# RF-PCB.net
KiCad netlist of a schematic drawn in EAGLE
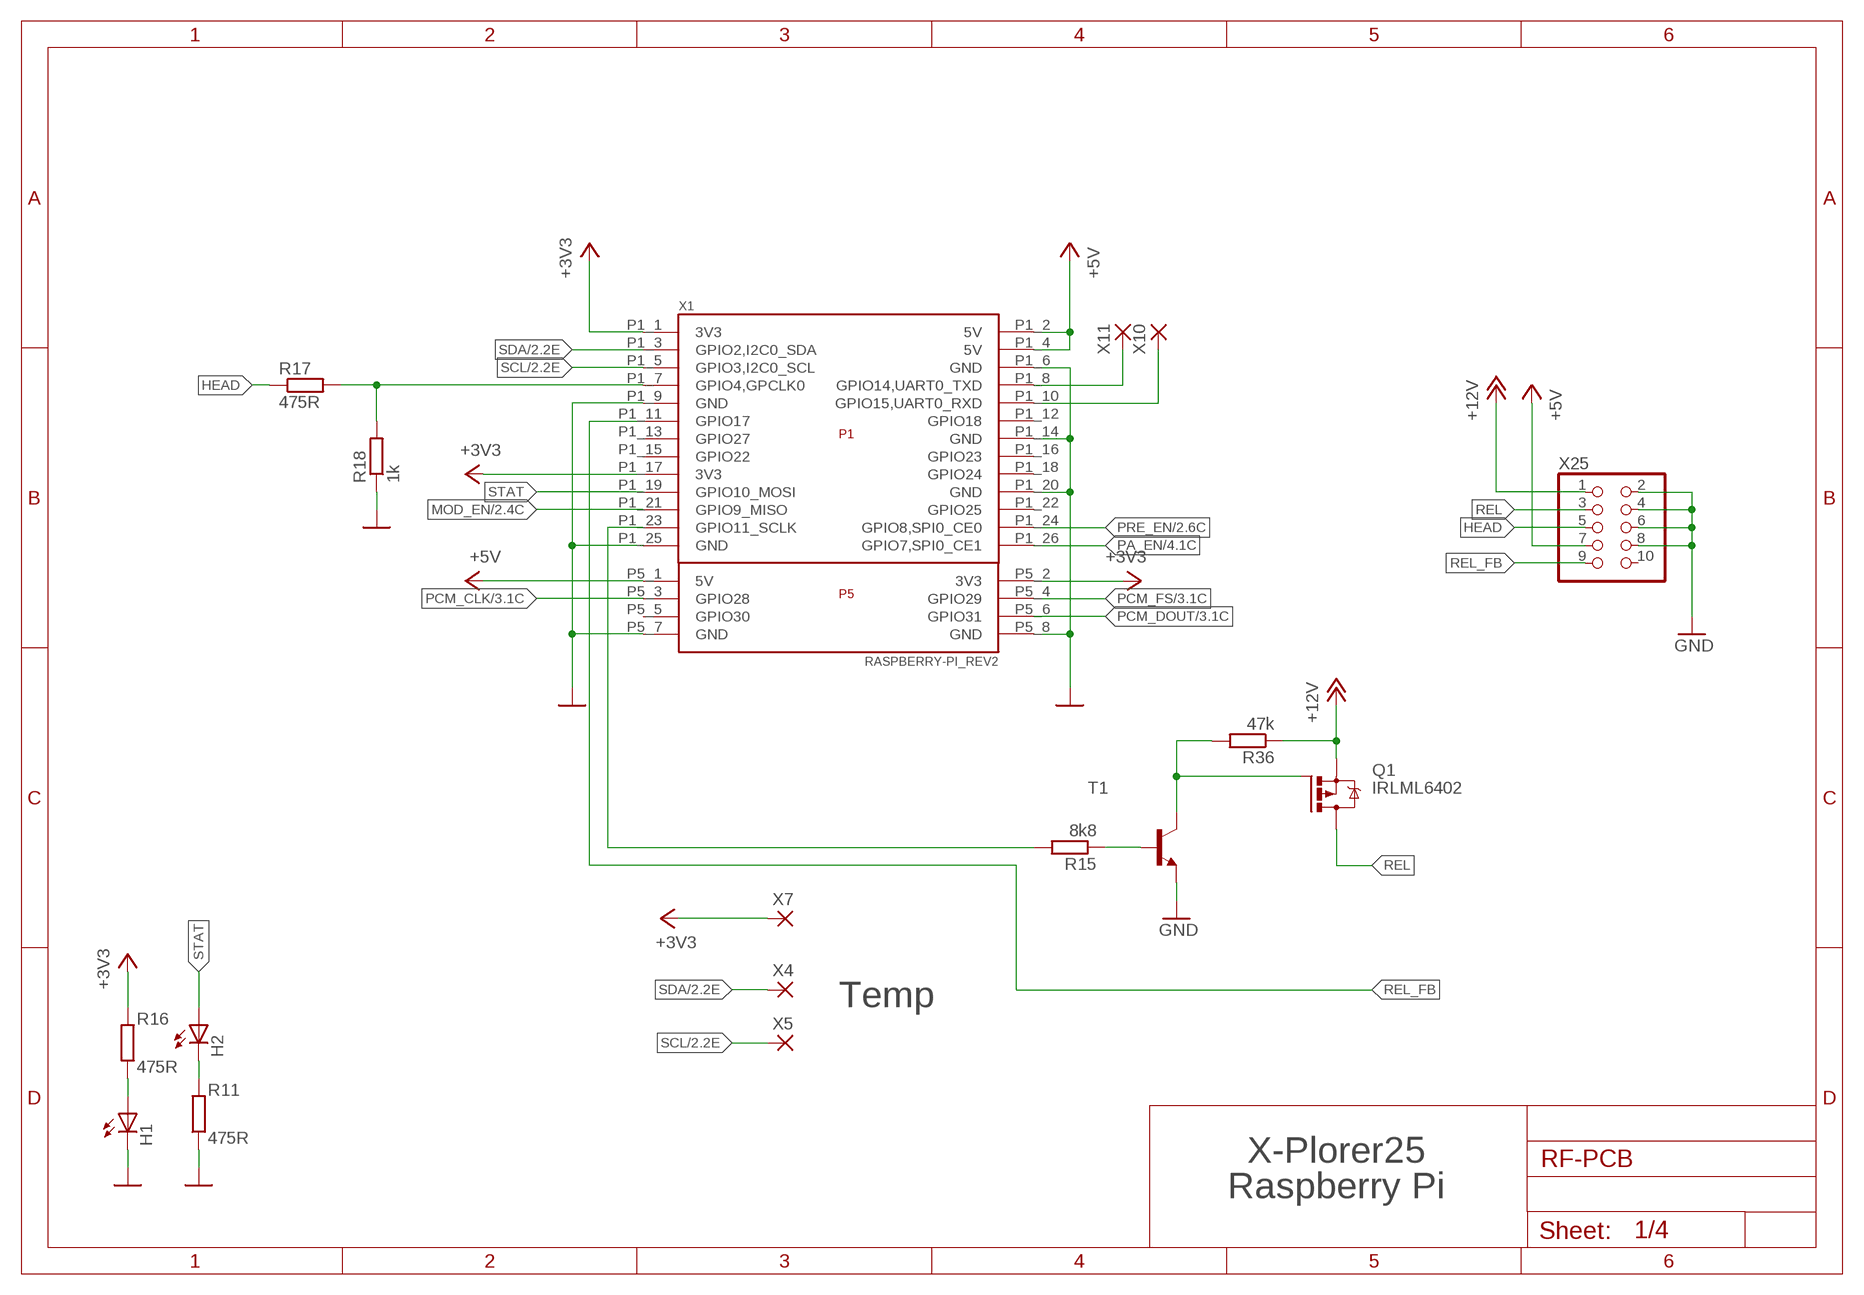
[diagram p0: schematic, sheet 1]
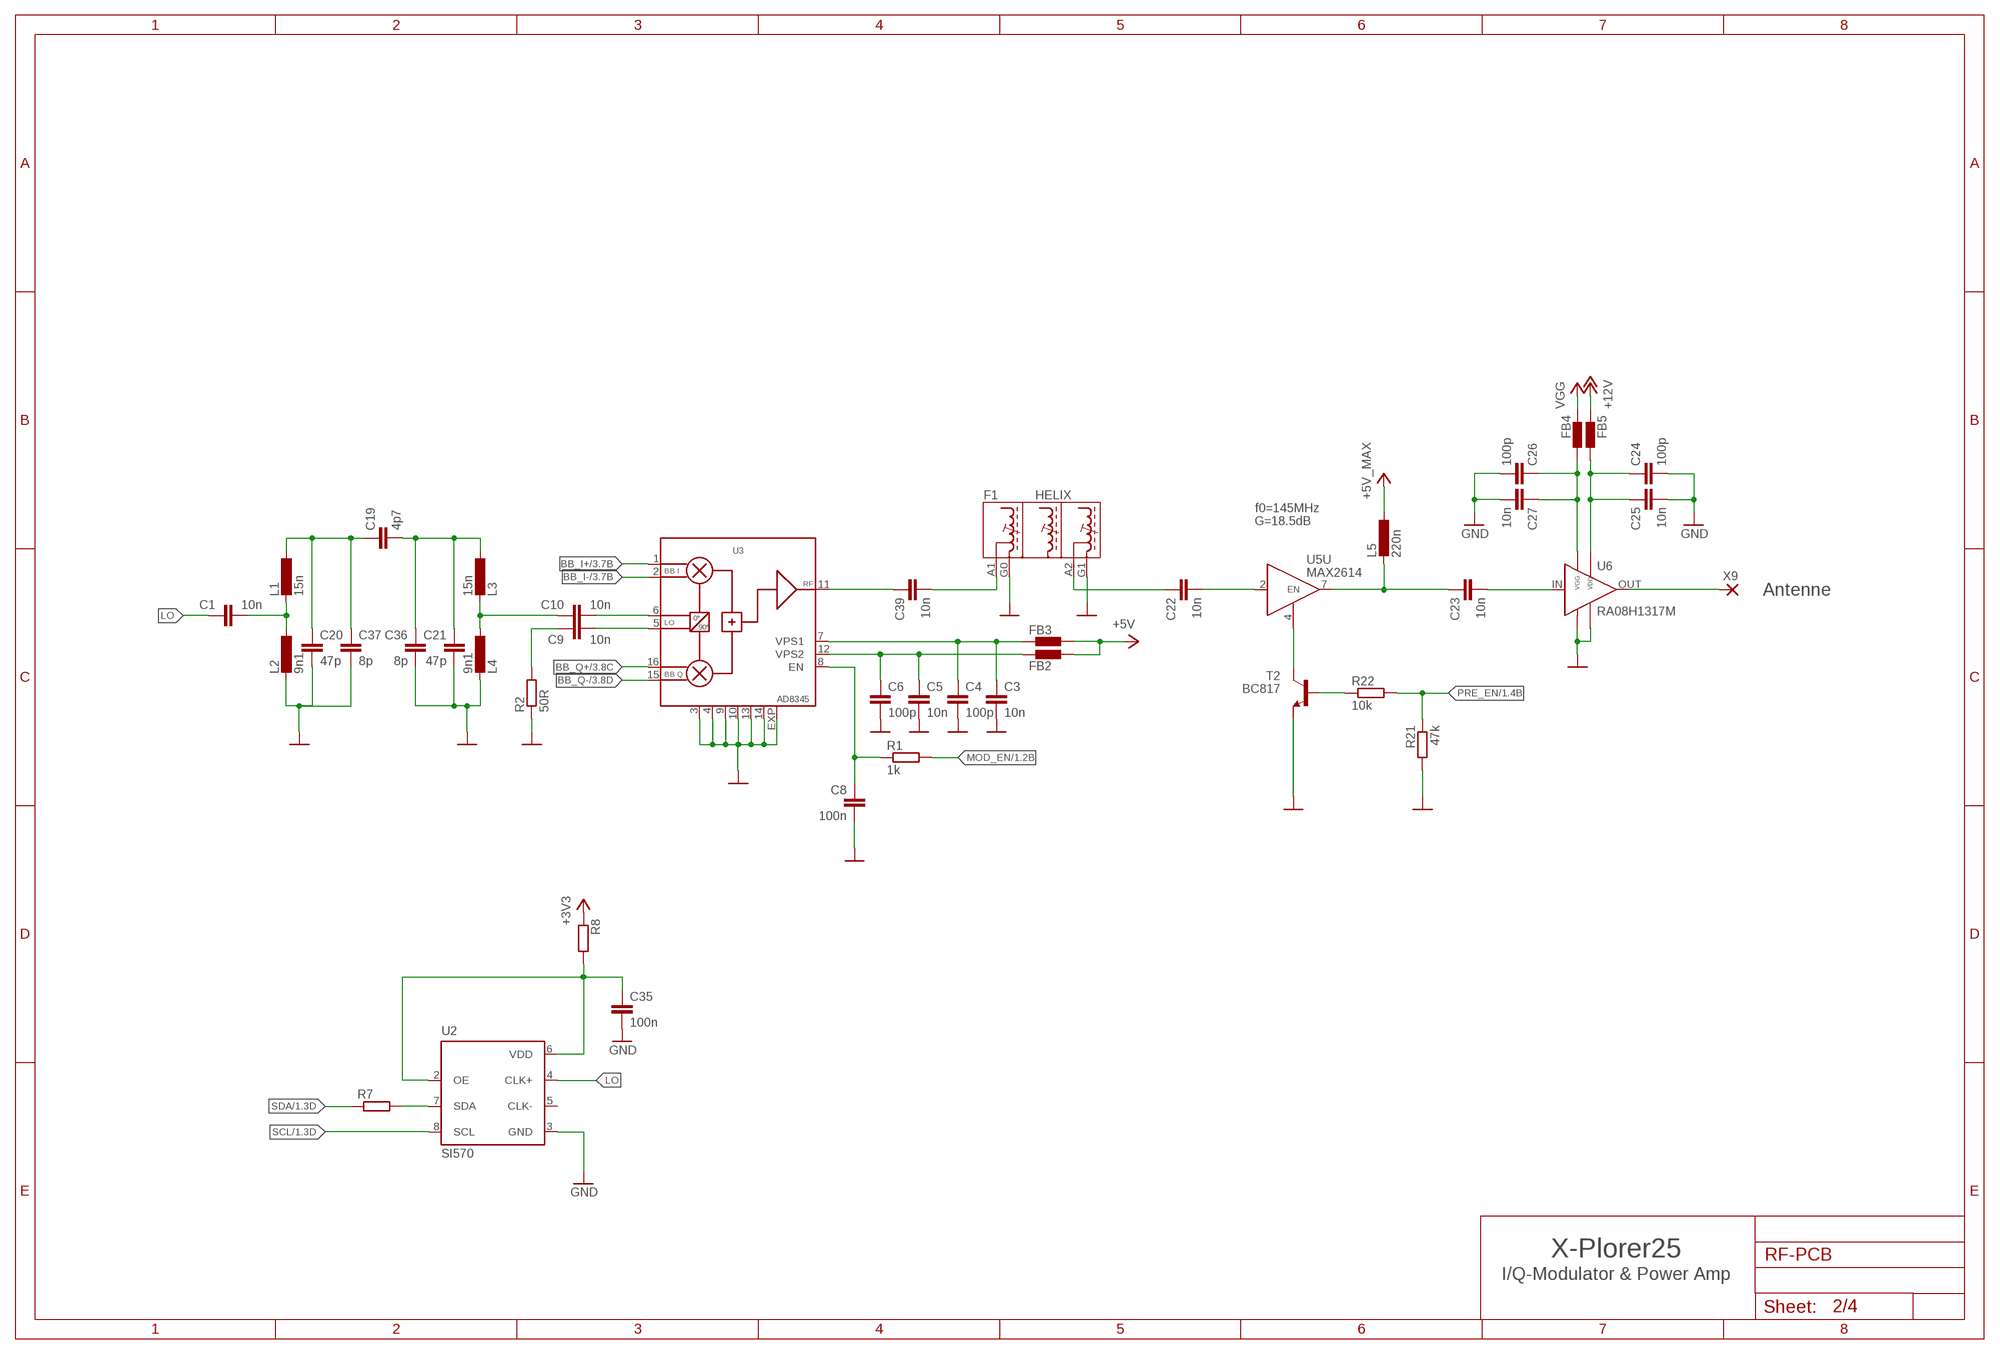
[diagram p1: schematic, sheet 2]
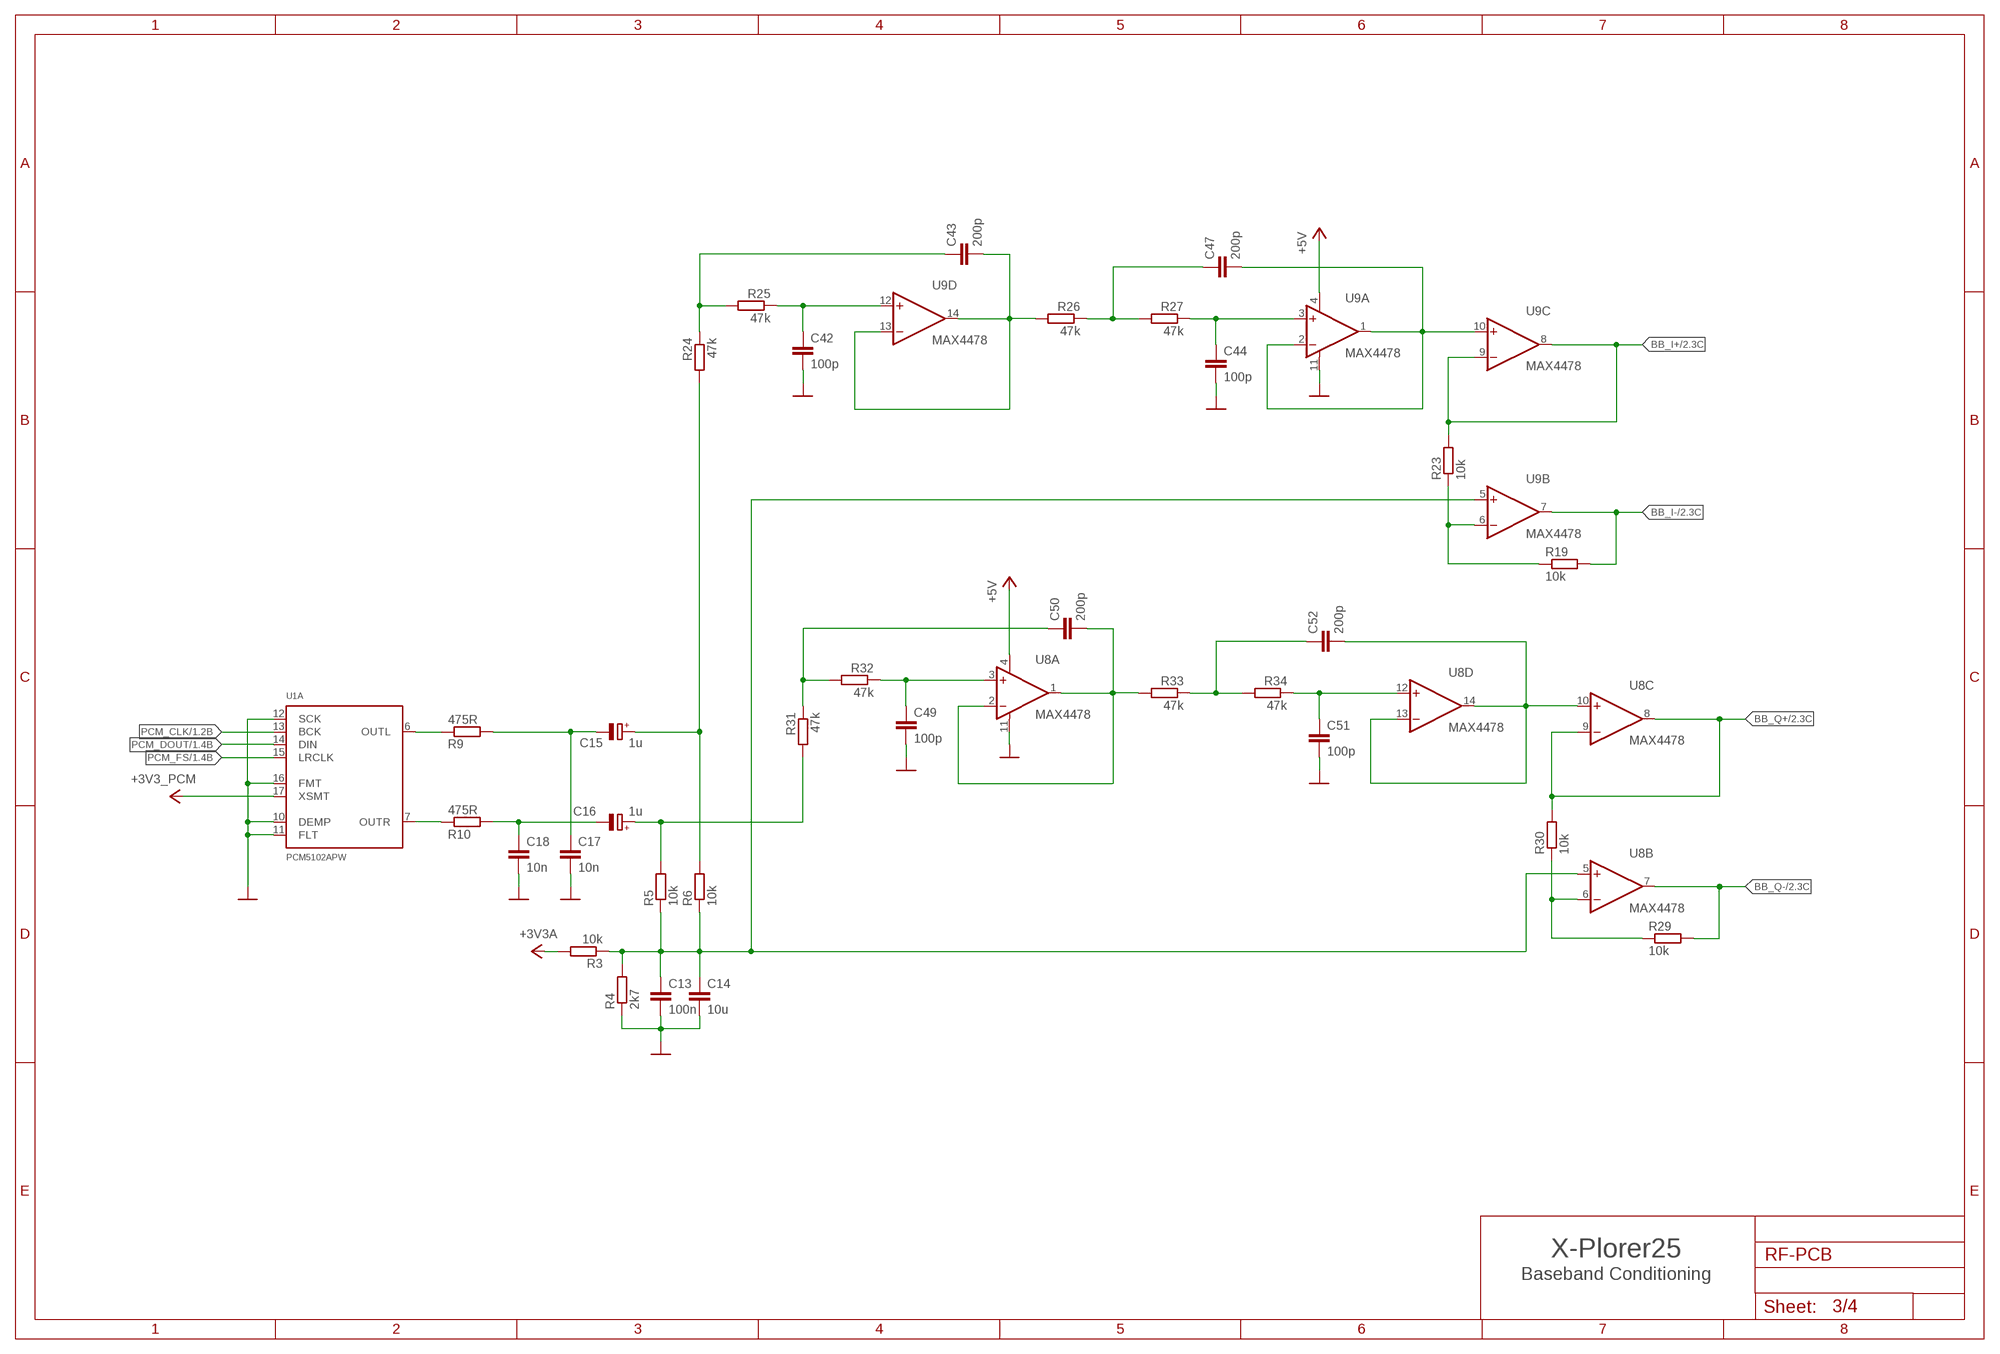
[diagram p2: schematic, sheet 3]
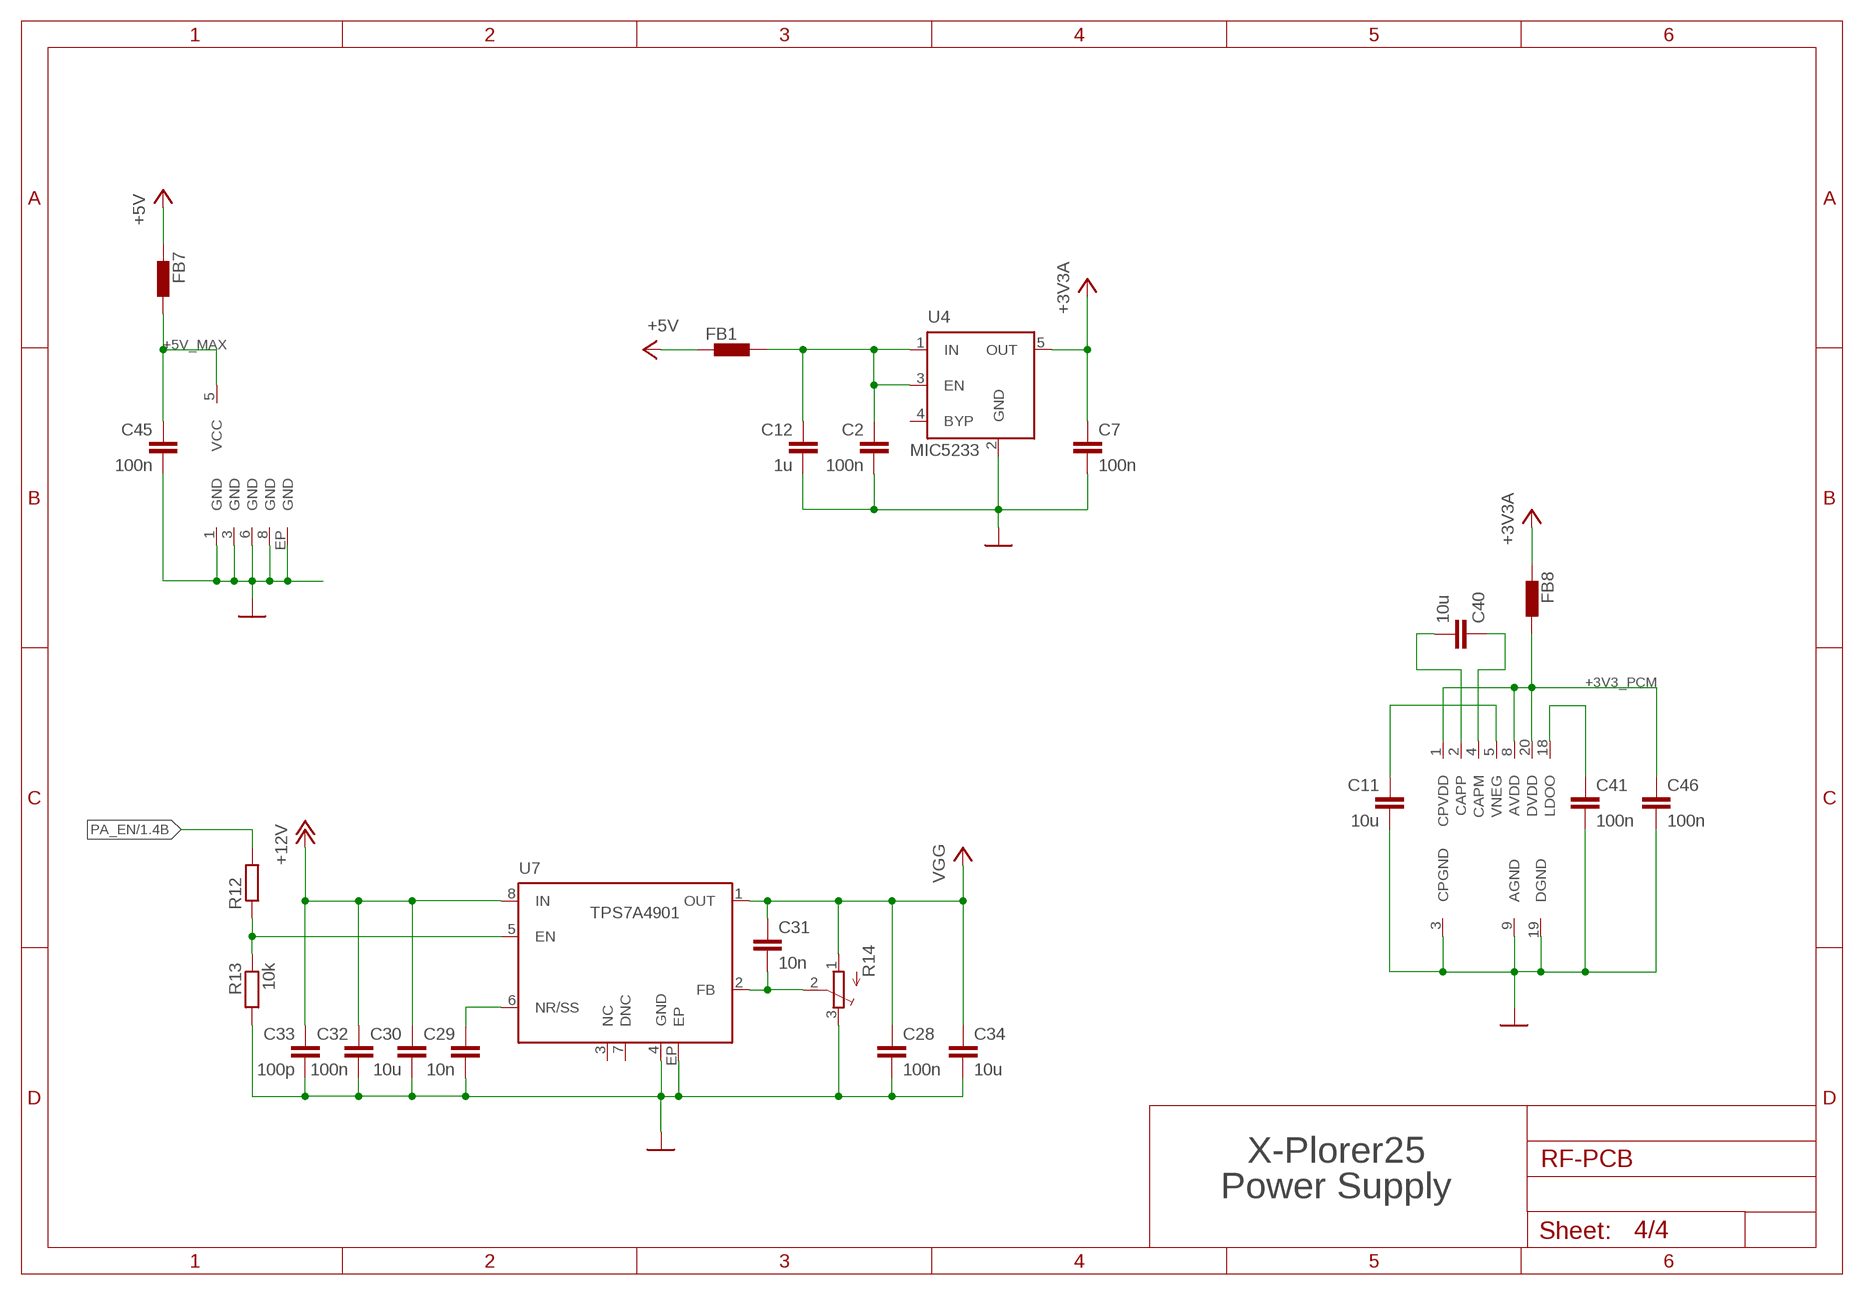
[diagram p3: schematic, sheet 4]

(export (version "E")
  (design (tool "Eeschema 10.0.6"))
  (components
    (comp (ref "C13")
      (value "100n")
      (footprint "eagle-import:C0603")
      (libsource (lib "eagle-import") (part "C-EUC0603"))
    )
    (comp (ref "C14")
      (value "10u")
      (footprint "eagle-import:C0603")
      (libsource (lib "eagle-import") (part "C-EUC0603"))
    )
    (comp (ref "C15")
      (value "1u")
      (footprint "eagle-import:CT3528")
      (libsource (lib "eagle-import") (part "CPOL-EUCT3528"))
    )
    (comp (ref "C16")
      (value "1u")
      (footprint "eagle-import:CT3528")
      (libsource (lib "eagle-import") (part "CPOL-EUCT3528"))
    )
    (comp (ref "C17")
      (value "10n")
      (footprint "eagle-import:C0603")
      (libsource (lib "eagle-import") (part "C-EUC0603"))
    )
    (comp (ref "C18")
      (value "10n")
      (footprint "eagle-import:C0603")
      (libsource (lib "eagle-import") (part "C-EUC0603"))
    )
    (comp (ref "C42")
      (value "100p")
      (footprint "eagle-import:C0603")
      (libsource (lib "eagle-import") (part "C-EUC0603"))
    )
    (comp (ref "C43")
      (value "200p")
      (footprint "eagle-import:C0805")
      (libsource (lib "eagle-import") (part "C-EUC0805"))
    )
    (comp (ref "C44")
      (value "100p")
      (footprint "eagle-import:C0603")
      (libsource (lib "eagle-import") (part "C-EUC0603"))
    )
    (comp (ref "C47")
      (value "200p")
      (footprint "eagle-import:C0805")
      (libsource (lib "eagle-import") (part "C-EUC0805"))
    )
    (comp (ref "C49")
      (value "100p")
      (footprint "eagle-import:C0603")
      (libsource (lib "eagle-import") (part "C-EUC0603"))
    )
    (comp (ref "C50")
      (value "200p")
      (footprint "eagle-import:C0805")
      (libsource (lib "eagle-import") (part "C-EUC0805"))
    )
    (comp (ref "C51")
      (value "100p")
      (footprint "eagle-import:C0603")
      (libsource (lib "eagle-import") (part "C-EUC0603"))
    )
    (comp (ref "C52")
      (value "200p")
      (footprint "eagle-import:C0805")
      (libsource (lib "eagle-import") (part "C-EUC0805"))
    )
    (comp (ref "R3")
      (value "10k")
      (footprint "eagle-import:R0603")
      (libsource (lib "eagle-import") (part "R-EU_R0603"))
    )
    (comp (ref "R4")
      (value "2k7")
      (footprint "eagle-import:R0603")
      (libsource (lib "eagle-import") (part "R-EU_R0603"))
    )
    (comp (ref "R5")
      (value "10k")
      (footprint "eagle-import:R0603")
      (libsource (lib "eagle-import") (part "R-EU_R0603"))
    )
    (comp (ref "R6")
      (value "10k")
      (footprint "eagle-import:R0603")
      (libsource (lib "eagle-import") (part "R-EU_R0603"))
    )
    (comp (ref "R9")
      (value "475R")
      (footprint "eagle-import:R0603")
      (libsource (lib "eagle-import") (part "R-EU_R0603"))
    )
    (comp (ref "R10")
      (value "475R")
      (footprint "eagle-import:R0603")
      (libsource (lib "eagle-import") (part "R-EU_R0603"))
    )
    (comp (ref "R19")
      (value "10k")
      (footprint "eagle-import:R0603")
      (libsource (lib "eagle-import") (part "R-EU_R0603"))
    )
    (comp (ref "R23")
      (value "10k")
      (footprint "eagle-import:R0603")
      (libsource (lib "eagle-import") (part "R-EU_R0603"))
    )
    (comp (ref "R24")
      (value "47k")
      (footprint "eagle-import:R0603")
      (libsource (lib "eagle-import") (part "R-EU_R0603"))
    )
    (comp (ref "R25")
      (value "47k")
      (footprint "eagle-import:R0603")
      (libsource (lib "eagle-import") (part "R-EU_R0603"))
    )
    (comp (ref "R26")
      (value "47k")
      (footprint "eagle-import:R0603")
      (libsource (lib "eagle-import") (part "R-EU_R0603"))
    )
    (comp (ref "R27")
      (value "47k")
      (footprint "eagle-import:R0603")
      (libsource (lib "eagle-import") (part "R-EU_R0603"))
    )
    (comp (ref "R29")
      (value "10k")
      (footprint "eagle-import:R0603")
      (libsource (lib "eagle-import") (part "R-EU_R0603"))
    )
    (comp (ref "R30")
      (value "10k")
      (footprint "eagle-import:R0603")
      (libsource (lib "eagle-import") (part "R-EU_R0603"))
    )
    (comp (ref "R31")
      (value "47k")
      (footprint "eagle-import:R0603")
      (libsource (lib "eagle-import") (part "R-EU_R0603"))
    )
    (comp (ref "R32")
      (value "47k")
      (footprint "eagle-import:R0603")
      (libsource (lib "eagle-import") (part "R-EU_R0603"))
    )
    (comp (ref "R33")
      (value "47k")
      (footprint "eagle-import:R0603")
      (libsource (lib "eagle-import") (part "R-EU_R0603"))
    )
    (comp (ref "R34")
      (value "47k")
      (footprint "eagle-import:R0603")
      (libsource (lib "eagle-import") (part "R-EU_R0603"))
    )
    (comp (ref "U1")
      (value "PCM5102APW")
      (footprint "eagle-import:PW_R-PDSO-G20")
      (libsource (lib "eagle-import") (part "PCM5102APW"))
    )
    (comp (ref "U8")
      (value "MAX4478")
      (footprint "eagle-import:SO14")
      (fields
        (field (name "MF") "TEXAS INSTRUMENTS")
        (field (name "MPN") "OPA4132UA")
        (field (name "MF_1") "TEXAS INSTRUMENTS")
        (field (name "MPN_1") "OPA4132UA")
        (field (name "OC_FARNELL") "1212302")
        (field (name "OC_NEWARK") "80K6028")
      )
      (libsource (lib "eagle-import") (part "OPA4132U"))
    )
    (comp (ref "U9")
      (value "MAX4478")
      (footprint "eagle-import:SO14")
      (fields (field (name "MF") "TEXAS INSTRUMENTS") (field (name "MPN") "OPA4132UA"))
      (libsource (lib "eagle-import") (part "OPA4132U"))
    )
    (comp (ref "C1")
      (value "10n")
      (footprint "eagle-import:C0603")
      (libsource (lib "eagle-import") (part "C-EUC0603"))
    )
    (comp (ref "C3")
      (value "10n")
      (footprint "eagle-import:C0603")
      (libsource (lib "eagle-import") (part "C-EUC0603"))
    )
    (comp (ref "C4")
      (value "100p")
      (footprint "eagle-import:C0603")
      (libsource (lib "eagle-import") (part "C-EUC0603"))
    )
    (comp (ref "C5")
      (value "10n")
      (footprint "eagle-import:C0603")
      (libsource (lib "eagle-import") (part "C-EUC0603"))
    )
    (comp (ref "C6")
      (value "100p")
      (footprint "eagle-import:C0603")
      (libsource (lib "eagle-import") (part "C-EUC0603"))
    )
    (comp (ref "C8")
      (value "100n")
      (footprint "eagle-import:C0603")
      (libsource (lib "eagle-import") (part "C-EUC0603"))
    )
    (comp (ref "C9")
      (value "10n")
      (footprint "eagle-import:C0603")
      (libsource (lib "eagle-import") (part "C-EUC0603"))
    )
    (comp (ref "C10")
      (value "10n")
      (footprint "eagle-import:C0603")
      (libsource (lib "eagle-import") (part "C-EUC0603"))
    )
    (comp (ref "C19")
      (value "4p7")
      (footprint "eagle-import:C0603")
      (libsource (lib "eagle-import") (part "C-EUC0603"))
    )
    (comp (ref "C20")
      (value "47p")
      (footprint "eagle-import:C0805K")
      (libsource (lib "eagle-import") (part "C-EUC0805K"))
    )
    (comp (ref "C21")
      (value "47p")
      (footprint "eagle-import:C0805K")
      (libsource (lib "eagle-import") (part "C-EUC0805K"))
    )
    (comp (ref "C22")
      (value "10n")
      (footprint "eagle-import:C0603")
      (libsource (lib "eagle-import") (part "C-EUC0603"))
    )
    (comp (ref "C23")
      (value "10n")
      (footprint "eagle-import:C0603")
      (libsource (lib "eagle-import") (part "C-EUC0603"))
    )
    (comp (ref "C24")
      (value "100p")
      (footprint "eagle-import:C0603")
      (libsource (lib "eagle-import") (part "C-EUC0603"))
    )
    (comp (ref "C25")
      (value "10n")
      (footprint "eagle-import:C0603")
      (libsource (lib "eagle-import") (part "C-EUC0603"))
    )
    (comp (ref "C26")
      (value "100p")
      (footprint "eagle-import:C0603")
      (libsource (lib "eagle-import") (part "C-EUC0603"))
    )
    (comp (ref "C27")
      (value "10n")
      (footprint "eagle-import:C0603")
      (libsource (lib "eagle-import") (part "C-EUC0603"))
    )
    (comp (ref "C35")
      (value "100n")
      (footprint "eagle-import:0603")
      (libsource (lib "eagle-import") (part "C-0603"))
    )
    (comp (ref "C36")
      (value "8p")
      (footprint "eagle-import:C0805K")
      (libsource (lib "eagle-import") (part "C-EUC0805K"))
    )
    (comp (ref "C37")
      (value "8p")
      (footprint "eagle-import:C0805K")
      (libsource (lib "eagle-import") (part "C-EUC0805K"))
    )
    (comp (ref "C39")
      (value "10n")
      (footprint "eagle-import:C0603")
      (libsource (lib "eagle-import") (part "C-EUC0603"))
    )
    (comp (ref "F1")
      (value "HELIX")
      (footprint "eagle-import:CBT13")
      (libsource (lib "eagle-import") (part "HELIX"))
    )
    (comp (ref "FB2")
      (value "BML15H")
      (footprint "eagle-import:R0603")
      (libsource (lib "eagle-import") (part "BML15H"))
    )
    (comp (ref "FB3")
      (value "BML15H")
      (footprint "eagle-import:R0603")
      (libsource (lib "eagle-import") (part "BML15H"))
    )
    (comp (ref "FB4")
      (value "BML15H")
      (footprint "eagle-import:R0603")
      (libsource (lib "eagle-import") (part "BML15H"))
    )
    (comp (ref "FB5")
      (value "BML15H")
      (footprint "eagle-import:R0603")
      (libsource (lib "eagle-import") (part "BML15H"))
    )
    (comp (ref "L1")
      (value "15n")
      (footprint "eagle-import:L2012C")
      (libsource (lib "eagle-import") (part "L-EUL2012C"))
    )
    (comp (ref "L2")
      (value "9n1")
      (footprint "eagle-import:L2012C")
      (libsource (lib "eagle-import") (part "L-EUL2012C"))
    )
    (comp (ref "L3")
      (value "15n")
      (footprint "eagle-import:L2012C")
      (libsource (lib "eagle-import") (part "L-EUL2012C"))
    )
    (comp (ref "L4")
      (value "9n1")
      (footprint "eagle-import:L2012C")
      (libsource (lib "eagle-import") (part "L-EUL2012C"))
    )
    (comp (ref "L5")
      (value "220n")
      (footprint "eagle-import:L2012C")
      (libsource (lib "eagle-import") (part "L-EUL2012C"))
    )
    (comp (ref "R1")
      (value "1k")
      (footprint "eagle-import:R0603")
      (libsource (lib "eagle-import") (part "R-EU_R0603"))
    )
    (comp (ref "R2")
      (value "50R")
      (footprint "eagle-import:R0603")
      (libsource (lib "eagle-import") (part "R-EU_R0603"))
    )
    (comp (ref "R7")
      (value "R-EU_R0603")
      (footprint "eagle-import:R0603")
      (libsource (lib "eagle-import") (part "R-EU_R0603"))
    )
    (comp (ref "R8")
      (value "R-EU_R2010")
      (footprint "eagle-import:R2010")
      (libsource (lib "eagle-import") (part "R-EU_R2010"))
    )
    (comp (ref "R21")
      (value "47k")
      (footprint "eagle-import:R0603")
      (libsource (lib "eagle-import") (part "R-EU_R0603"))
    )
    (comp (ref "R22")
      (value "10k")
      (footprint "eagle-import:R0603")
      (libsource (lib "eagle-import") (part "R-EU_R0603"))
    )
    (comp (ref "T2")
      (value "BC817")
      (footprint "eagle-import:SOT23-BEC")
      (libsource (lib "eagle-import") (part "BC817SMD-16LT1"))
    )
    (comp (ref "U2")
      (value "SI570")
      (footprint "eagle-import:8-PIN")
      (libsource (lib "eagle-import") (part "SI570"))
    )
    (comp (ref "U3")
      (value "AD8345")
      (footprint "eagle-import:TSSOP16EXP")
      (libsource (lib "eagle-import") (part "AD8345"))
    )
    (comp (ref "U5")
      (value "MAX2614")
      (footprint "eagle-import:TDFN8-2X3MM")
      (libsource (lib "eagle-import") (part "MAX2615"))
    )
    (comp (ref "U6")
      (value "RA08H1317M")
      (footprint "eagle-import:RA08H1317M")
      (libsource (lib "eagle-import") (part "RA08H1317M"))
    )
    (comp (ref "X9")
      (value "SMD2")
      (footprint "eagle-import:SMD1,27-2,54")
      (libsource (lib "eagle-import") (part "SMD2"))
    )
    (comp (ref "H1")
      (value "PL006-WCR12")
      (footprint "eagle-import:SOT23")
      (libsource (lib "eagle-import") (part "PL006-WCR12"))
    )
    (comp (ref "H2")
      (value "PL006-WCR12")
      (footprint "eagle-import:SOT23")
      (libsource (lib "eagle-import") (part "PL006-WCR12"))
    )
    (comp (ref "Q1")
      (value "IRLML6402")
      (footprint "eagle-import:MICRO3")
      (libsource (lib "eagle-import") (part "IRLML5203"))
    )
    (comp (ref "R11")
      (value "475R")
      (footprint "eagle-import:R0603")
      (libsource (lib "eagle-import") (part "R-EU_R0603"))
    )
    (comp (ref "R15")
      (value "8k8")
      (footprint "eagle-import:R0603")
      (libsource (lib "eagle-import") (part "R-EU_R0603"))
    )
    (comp (ref "R16")
      (value "475R")
      (footprint "eagle-import:R0603")
      (libsource (lib "eagle-import") (part "R-EU_R0603"))
    )
    (comp (ref "R17")
      (value "475R")
      (footprint "eagle-import:R0603")
      (libsource (lib "eagle-import") (part "R-EU_R0603"))
    )
    (comp (ref "R18")
      (value "1k")
      (footprint "eagle-import:R0603")
      (libsource (lib "eagle-import") (part "R-EU_R0603"))
    )
    (comp (ref "R36")
      (value "47k")
      (footprint "eagle-import:R0603")
      (libsource (lib "eagle-import") (part "R-EU_R0603"))
    )
    (comp (ref "T1")
      (value "BC817-16-NPN-SOT23-BEC")
      (footprint "eagle-import:SOT23-BEC")
      (libsource (lib "eagle-import") (part "-NPN-SOT23-BECBC817-16"))
    )
    (comp (ref "X1")
      (value "RASPBERRY-PI_REV2")
      (footprint "eagle-import:RASPBERRY-PI_REV2")
      (libsource (lib "eagle-import") (part "RASPBERRY-PI_REV2"))
    )
    (comp (ref "X4")
      (value "SMD2")
      (footprint "eagle-import:SMD1,27-2,54")
      (libsource (lib "eagle-import") (part "SMD2"))
    )
    (comp (ref "X5")
      (value "SMD2")
      (footprint "eagle-import:SMD1,27-2,54")
      (libsource (lib "eagle-import") (part "SMD2"))
    )
    (comp (ref "X7")
      (value "SMD2")
      (footprint "eagle-import:SMD1,27-2,54")
      (libsource (lib "eagle-import") (part "SMD2"))
    )
    (comp (ref "X10")
      (value "SMD2")
      (footprint "eagle-import:SMD1,27-2,54")
      (libsource (lib "eagle-import") (part "SMD2"))
    )
    (comp (ref "X11")
      (value "SMD2")
      (footprint "eagle-import:SMD1,27-2,54")
      (libsource (lib "eagle-import") (part "SMD2"))
    )
    (comp (ref "X25")
      (value "PINHD-2X5")
      (footprint "eagle-import:2X05")
      (libsource (lib "eagle-import") (part "PINHD-2X5"))
    )
    (comp (ref "C2")
      (value "100n")
      (footprint "eagle-import:C0603")
      (libsource (lib "eagle-import") (part "C-EUC0603"))
    )
    (comp (ref "C7")
      (value "100n")
      (footprint "eagle-import:C0603")
      (libsource (lib "eagle-import") (part "C-EUC0603"))
    )
    (comp (ref "C11")
      (value "10u")
      (footprint "eagle-import:C0805")
      (libsource (lib "eagle-import") (part "C-EUC0805"))
    )
    (comp (ref "C12")
      (value "1u")
      (footprint "eagle-import:C0603")
      (libsource (lib "eagle-import") (part "C-EUC0603"))
    )
    (comp (ref "C28")
      (value "100n")
      (footprint "eagle-import:C0603")
      (libsource (lib "eagle-import") (part "C-EUC0603"))
    )
    (comp (ref "C29")
      (value "10n")
      (footprint "eagle-import:C0603K")
      (libsource (lib "eagle-import") (part "C-EUC0603K"))
    )
    (comp (ref "C30")
      (value "10u")
      (footprint "eagle-import:C0805")
      (libsource (lib "eagle-import") (part "C-EUC0805"))
    )
    (comp (ref "C31")
      (value "10n")
      (footprint "eagle-import:C0603")
      (libsource (lib "eagle-import") (part "C-EUC0603"))
    )
    (comp (ref "C32")
      (value "100n")
      (footprint "eagle-import:C0603")
      (libsource (lib "eagle-import") (part "C-EUC0603"))
    )
    (comp (ref "C33")
      (value "100p")
      (footprint "eagle-import:C0603")
      (libsource (lib "eagle-import") (part "C-EUC0603"))
    )
    (comp (ref "C34")
      (value "10u")
      (footprint "eagle-import:C0805")
      (libsource (lib "eagle-import") (part "C-EUC0805"))
    )
    (comp (ref "C40")
      (value "10u")
      (footprint "eagle-import:C0805")
      (libsource (lib "eagle-import") (part "C-EUC0805"))
    )
    (comp (ref "C41")
      (value "100n")
      (footprint "eagle-import:C0603")
      (libsource (lib "eagle-import") (part "C-EUC0603"))
    )
    (comp (ref "C45")
      (value "100n")
      (footprint "eagle-import:C0603")
      (libsource (lib "eagle-import") (part "C-EUC0603"))
    )
    (comp (ref "C46")
      (value "100n")
      (footprint "eagle-import:C0603")
      (libsource (lib "eagle-import") (part "C-EUC0603"))
    )
    (comp (ref "FB1")
      (value "BML15H")
      (footprint "eagle-import:R0603")
      (libsource (lib "eagle-import") (part "BML15H"))
    )
    (comp (ref "FB7")
      (value "BML15H")
      (footprint "eagle-import:R0603")
      (libsource (lib "eagle-import") (part "BML15H"))
    )
    (comp (ref "FB8")
      (value "BML15H")
      (footprint "eagle-import:R0603")
      (libsource (lib "eagle-import") (part "BML15H"))
    )
    (comp (ref "R12")
      (value "R-EU_R0603")
      (footprint "eagle-import:R0603")
      (libsource (lib "eagle-import") (part "R-EU_R0603"))
    )
    (comp (ref "R13")
      (value "10k")
      (footprint "eagle-import:R0603")
      (libsource (lib "eagle-import") (part "R-EU_R0603"))
    )
    (comp (ref "R14")
      (value "TRIM_EU-SM-42/43X")
      (footprint "eagle-import:SM-42_43X")
      (libsource (lib "eagle-import") (part "TRIM_EU-SM-42/43X"))
    )
    (comp (ref "U4")
      (value "MIC5233")
      (footprint "eagle-import:SOT23-5")
      (libsource (lib "eagle-import") (part "MIC5219XX"))
    )
    (comp (ref "U7")
      (value "TPS7A4901")
      (footprint "eagle-import:PW_R-PDSO-G08")
      (libsource (lib "eagle-import") (part "TPS7A4901"))
    )
  )
  (nets
    (net (code "1") (name "+3V3") (class "Default")
      (node (ref "R16") (pin "2") (pinfunction "2_2") (pintype "passive"))
      (node (ref "R8") (pin "1") (pinfunction "1_1") (pintype "passive"))
      (node (ref "X1") (pin "P1_1") (pinfunction "3V3_P1_1") (pintype "bidirectional"))
      (node (ref "X1") (pin "P1_17") (pinfunction "3V3_P1_17") (pintype "bidirectional"))
      (node (ref "X1") (pin "P5_2") (pinfunction "3V3_P5_2") (pintype "bidirectional"))
      (node (ref "X7") (pin "1") (pinfunction "P_1") (pintype "passive"))
    )
    (net (code "2") (name "+3V3A") (class "Default")
      (node (ref "C7") (pin "1") (pinfunction "1_1") (pintype "passive"))
      (node (ref "FB8") (pin "1") (pinfunction "1_1") (pintype "passive"))
      (node (ref "R3") (pin "2") (pinfunction "2_2") (pintype "passive"))
      (node (ref "U4") (pin "5") (pinfunction "OUT_5") (pintype "output"))
    )
    (net (code "3") (name "+3V3_PCM") (class "Default")
      (node (ref "C46") (pin "1") (pinfunction "1_1") (pintype "passive"))
      (node (ref "FB8") (pin "2") (pinfunction "2_2") (pintype "passive"))
      (node (ref "U1") (pin "1") (pinfunction "CPVDD_1") (pintype "power_in"))
      (node (ref "U1") (pin "17") (pinfunction "XSMT_17") (pintype "input"))
      (node (ref "U1") (pin "20") (pinfunction "DVDD_20") (pintype "power_in"))
      (node (ref "U1") (pin "8") (pinfunction "AVDD_8") (pintype "power_in"))
    )
    (net (code "4") (name "+5V") (class "Default")
      (node (ref "FB1") (pin "1") (pinfunction "1_1") (pintype "passive"))
      (node (ref "FB2") (pin "2") (pinfunction "2_2") (pintype "passive"))
      (node (ref "FB3") (pin "2") (pinfunction "2_2") (pintype "passive"))
      (node (ref "FB7") (pin "1") (pinfunction "1_1") (pintype "passive"))
      (node (ref "U8") (pin "4") (pinfunction "V+_4") (pintype "power_in"))
      (node (ref "U9") (pin "4") (pinfunction "V+_4") (pintype "power_in"))
      (node (ref "X1") (pin "P1_2") (pinfunction "5V_P1_2") (pintype "bidirectional"))
      (node (ref "X1") (pin "P1_4") (pinfunction "5V_P1_4") (pintype "bidirectional"))
      (node (ref "X1") (pin "P5_1") (pinfunction "5V_P5_1") (pintype "bidirectional"))
      (node (ref "X25") (pin "7") (pinfunction "7_7") (pintype "passive"))
    )
    (net (code "5") (name "+5V_MAX") (class "Default")
      (node (ref "C45") (pin "1") (pinfunction "1_1") (pintype "passive"))
      (node (ref "FB7") (pin "2") (pinfunction "2_2") (pintype "passive"))
      (node (ref "L5") (pin "1") (pinfunction "1_1") (pintype "passive"))
      (node (ref "U5") (pin "5") (pinfunction "VCC_5") (pintype "power_in"))
    )
    (net (code "6") (name "+12V") (class "Default")
      (node (ref "C30") (pin "1") (pinfunction "1_1") (pintype "passive"))
      (node (ref "C32") (pin "1") (pinfunction "1_1") (pintype "passive"))
      (node (ref "C33") (pin "1") (pinfunction "1_1") (pintype "passive"))
      (node (ref "FB5") (pin "1") (pinfunction "1_1") (pintype "passive"))
      (node (ref "Q1") (pin "2") (pinfunction "S_2") (pintype "passive"))
      (node (ref "R36") (pin "1") (pinfunction "1_1") (pintype "passive"))
      (node (ref "U7") (pin "8") (pinfunction "IN_8") (pintype "input"))
      (node (ref "X25") (pin "1") (pinfunction "1_1") (pintype "passive"))
    )
    (net (code "7") (name "BB_I+") (class "Default")
      (node (ref "R23") (pin "2") (pinfunction "2_2") (pintype "passive"))
      (node (ref "U3") (pin "1") (pinfunction "BB_I_1") (pintype "input"))
      (node (ref "U9") (pin "8") (pinfunction "OUT_8") (pintype "output"))
      (node (ref "U9") (pin "9") (pinfunction "-IN_9") (pintype "input"))
    )
    (net (code "8") (name "BB_I-") (class "Default")
      (node (ref "R19") (pin "2") (pinfunction "2_2") (pintype "passive"))
      (node (ref "U3") (pin "2") (pinfunction "~{BB_I}_2") (pintype "input"))
      (node (ref "U9") (pin "7") (pinfunction "OUT_7") (pintype "output"))
    )
    (net (code "9") (name "BB_Q+") (class "Default")
      (node (ref "R30") (pin "2") (pinfunction "2_2") (pintype "passive"))
      (node (ref "U3") (pin "16") (pinfunction "BB_Q_16") (pintype "input"))
      (node (ref "U8") (pin "8") (pinfunction "OUT_8") (pintype "output"))
      (node (ref "U8") (pin "9") (pinfunction "-IN_9") (pintype "input"))
    )
    (net (code "10") (name "BB_Q-") (class "Default")
      (node (ref "R29") (pin "2") (pinfunction "2_2") (pintype "passive"))
      (node (ref "U3") (pin "15") (pinfunction "~{BB_Q}_15") (pintype "input"))
      (node (ref "U8") (pin "7") (pinfunction "OUT_7") (pintype "output"))
    )
    (net (code "11") (name "GND") (class "Default")
      (node (ref "C11") (pin "2") (pinfunction "2_2") (pintype "passive"))
      (node (ref "C12") (pin "2") (pinfunction "2_2") (pintype "passive"))
      (node (ref "C13") (pin "2") (pinfunction "2_2") (pintype "passive"))
      (node (ref "C14") (pin "2") (pinfunction "2_2") (pintype "passive"))
      (node (ref "C17") (pin "2") (pinfunction "2_2") (pintype "passive"))
      (node (ref "C18") (pin "2") (pinfunction "2_2") (pintype "passive"))
      (node (ref "C2") (pin "2") (pinfunction "2_2") (pintype "passive"))
      (node (ref "C20") (pin "2") (pinfunction "2_2") (pintype "passive"))
      (node (ref "C21") (pin "2") (pinfunction "2_2") (pintype "passive"))
      (node (ref "C24") (pin "2") (pinfunction "2_2") (pintype "passive"))
      (node (ref "C25") (pin "2") (pinfunction "2_2") (pintype "passive"))
      (node (ref "C26") (pin "2") (pinfunction "2_2") (pintype "passive"))
      (node (ref "C27") (pin "2") (pinfunction "2_2") (pintype "passive"))
      (node (ref "C28") (pin "2") (pinfunction "2_2") (pintype "passive"))
      (node (ref "C29") (pin "2") (pinfunction "2_2") (pintype "passive"))
      (node (ref "C3") (pin "2") (pinfunction "2_2") (pintype "passive"))
      (node (ref "C30") (pin "2") (pinfunction "2_2") (pintype "passive"))
      (node (ref "C32") (pin "2") (pinfunction "2_2") (pintype "passive"))
      (node (ref "C33") (pin "2") (pinfunction "2_2") (pintype "passive"))
      (node (ref "C34") (pin "2") (pinfunction "2_2") (pintype "passive"))
      (node (ref "C35") (pin "2") (pinfunction "2_2") (pintype "passive"))
      (node (ref "C36") (pin "2") (pinfunction "2_2") (pintype "passive"))
      (node (ref "C37") (pin "2") (pinfunction "2_2") (pintype "passive"))
      (node (ref "C4") (pin "2") (pinfunction "2_2") (pintype "passive"))
      (node (ref "C41") (pin "2") (pinfunction "2_2") (pintype "passive"))
      (node (ref "C42") (pin "2") (pinfunction "2_2") (pintype "passive"))
      (node (ref "C44") (pin "2") (pinfunction "2_2") (pintype "passive"))
      (node (ref "C45") (pin "2") (pinfunction "2_2") (pintype "passive"))
      (node (ref "C46") (pin "2") (pinfunction "2_2") (pintype "passive"))
      (node (ref "C49") (pin "2") (pinfunction "2_2") (pintype "passive"))
      (node (ref "C5") (pin "2") (pinfunction "2_2") (pintype "passive"))
      (node (ref "C51") (pin "2") (pinfunction "2_2") (pintype "passive"))
      (node (ref "C6") (pin "2") (pinfunction "2_2") (pintype "passive"))
      (node (ref "C7") (pin "2") (pinfunction "2_2") (pintype "passive"))
      (node (ref "C8") (pin "2") (pinfunction "2_2") (pintype "passive"))
      (node (ref "F1") (pin "G0") (pinfunction "GND_G0") (pintype "passive"))
      (node (ref "F1") (pin "G1") (pinfunction "GND_G1") (pintype "passive"))
      (node (ref "H1") (pin "3") (pinfunction "C_3") (pintype "passive"))
      (node (ref "L2") (pin "2") (pinfunction "2_2") (pintype "passive"))
      (node (ref "L4") (pin "2") (pinfunction "2_2") (pintype "passive"))
      (node (ref "R11") (pin "1") (pinfunction "1_1") (pintype "passive"))
      (node (ref "R13") (pin "2") (pinfunction "2_2") (pintype "passive"))
      (node (ref "R14") (pin "3") (pinfunction "E_3") (pintype "passive"))
      (node (ref "R18") (pin "1") (pinfunction "1_1") (pintype "passive"))
      (node (ref "R2") (pin "1") (pinfunction "1_1") (pintype "passive"))
      (node (ref "R21") (pin "2") (pinfunction "2_2") (pintype "passive"))
      (node (ref "R4") (pin "1") (pinfunction "1_1") (pintype "passive"))
      (node (ref "T1") (pin "E") (pinfunction "E_E") (pintype "passive"))
      (node (ref "T2") (pin "E") (pinfunction "E_E") (pintype "passive"))
      (node (ref "U1") (pin "10") (pinfunction "DEMP_10") (pintype "input"))
      (node (ref "U1") (pin "11") (pinfunction "FLT_11") (pintype "input"))
      (node (ref "U1") (pin "12") (pinfunction "SCK_12") (pintype "input"))
      (node (ref "U1") (pin "16") (pinfunction "FMT_16") (pintype "input"))
      (node (ref "U1") (pin "19") (pinfunction "DGND_19") (pintype "power_in"))
      (node (ref "U1") (pin "3") (pinfunction "CPGND_3") (pintype "power_in"))
      (node (ref "U1") (pin "9") (pinfunction "AGND_9") (pintype "power_in"))
      (node (ref "U2") (pin "3") (pinfunction "GND_3") (pintype "power_in"))
      (node (ref "U3") (pin "10") (pinfunction "GND_10") (pintype "power_in"))
      (node (ref "U3") (pin "13") (pinfunction "GND_13") (pintype "power_in"))
      (node (ref "U3") (pin "14") (pinfunction "GND_14") (pintype "power_in"))
      (node (ref "U3") (pin "3") (pinfunction "GND_3") (pintype "power_in"))
      (node (ref "U3") (pin "4") (pinfunction "GND_4") (pintype "power_in"))
      (node (ref "U3") (pin "9") (pinfunction "GND_9") (pintype "power_in"))
      (node (ref "U3") (pin "EXP") (pinfunction "GND_EXP") (pintype "power_in"))
      (node (ref "U4") (pin "2") (pinfunction "GND_2") (pintype "power_in"))
      (node (ref "U5") (pin "1") (pinfunction "GND_1") (pintype "power_in"))
      (node (ref "U5") (pin "3") (pinfunction "GND_3") (pintype "power_in"))
      (node (ref "U5") (pin "6") (pinfunction "GND_6") (pintype "power_in"))
      (node (ref "U5") (pin "8") (pinfunction "GND_8") (pintype "power_in"))
      (node (ref "U5") (pin "EP") (pinfunction "GND_EP") (pintype "power_in"))
      (node (ref "U6") (pin "G1") (pinfunction "GND_G1") (pintype "power_in"))
      (node (ref "U6") (pin "G2") (pinfunction "GND_G2") (pintype "power_in"))
      (node (ref "U7") (pin "4") (pinfunction "GND_4") (pintype "power_in"))
      (node (ref "U7") (pin "EP") (pinfunction "EP_EP") (pintype "passive"))
      (node (ref "U8") (pin "11") (pinfunction "V-_11") (pintype "power_in"))
      (node (ref "U9") (pin "11") (pinfunction "V-_11") (pintype "power_in"))
      (node (ref "X1") (pin "P1_14") (pinfunction "GND_P1_14") (pintype "bidirectional"))
      (node (ref "X1") (pin "P1_20") (pinfunction "GND_P1_20") (pintype "bidirectional"))
      (node (ref "X1") (pin "P1_25") (pinfunction "GND_P1_25") (pintype "bidirectional"))
      (node (ref "X1") (pin "P1_6") (pinfunction "GND_P1_6") (pintype "bidirectional"))
      (node (ref "X1") (pin "P1_9") (pinfunction "GND_P1_9") (pintype "bidirectional"))
      (node (ref "X1") (pin "P5_7") (pinfunction "GND_P5_7") (pintype "bidirectional"))
      (node (ref "X1") (pin "P5_8") (pinfunction "GND_P5_8") (pintype "bidirectional"))
      (node (ref "X25") (pin "2") (pinfunction "2_2") (pintype "passive"))
      (node (ref "X25") (pin "4") (pinfunction "4_4") (pintype "passive"))
      (node (ref "X25") (pin "6") (pinfunction "6_6") (pintype "passive"))
      (node (ref "X25") (pin "8") (pinfunction "8_8") (pintype "passive"))
    )
    (net (code "12") (name "HEAD") (class "Default")
      (node (ref "R17") (pin "1") (pinfunction "1_1") (pintype "passive"))
      (node (ref "X25") (pin "5") (pinfunction "5_5") (pintype "passive"))
    )
    (net (code "13") (name "LO") (class "Default")
      (node (ref "C1") (pin "1") (pinfunction "1_1") (pintype "passive"))
      (node (ref "U2") (pin "4") (pinfunction "CLK+_4") (pintype "output"))
    )
    (net (code "14") (name "MOD_EN") (class "Default")
      (node (ref "R1") (pin "2") (pinfunction "2_2") (pintype "passive"))
      (node (ref "X1") (pin "P1_21") (pinfunction "GPIO9_MISO_P1_21") (pintype "bidirectional"))
    )
    (net (code "15") (name "Net-(C1-Pad2)") (class "Default")
      (node (ref "C1") (pin "2") (pinfunction "2_2") (pintype "passive"))
      (node (ref "L1") (pin "2") (pinfunction "2_2") (pintype "passive"))
      (node (ref "L2") (pin "1") (pinfunction "1_1") (pintype "passive"))
    )
    (net (code "16") (name "Net-(C9-Pad1)") (class "Default")
      (node (ref "C9") (pin "1") (pinfunction "1_1") (pintype "passive"))
      (node (ref "R2") (pin "2") (pinfunction "2_2") (pintype "passive"))
    )
    (net (code "17") (name "Net-(C10-Pad1)") (class "Default")
      (node (ref "C10") (pin "1") (pinfunction "1_1") (pintype "passive"))
      (node (ref "L3") (pin "2") (pinfunction "2_2") (pintype "passive"))
      (node (ref "L4") (pin "1") (pinfunction "1_1") (pintype "passive"))
    )
    (net (code "18") (name "Net-(C15-Pad+)") (class "Default")
      (node (ref "C15") (pin "+") (pinfunction "+_+") (pintype "passive"))
      (node (ref "R24") (pin "2") (pinfunction "2_2") (pintype "passive"))
      (node (ref "R6") (pin "2") (pinfunction "2_2") (pintype "passive"))
    )
    (net (code "19") (name "Net-(C15-Pad-)") (class "Default")
      (node (ref "C15") (pin "-") (pinfunction "-_-") (pintype "passive"))
      (node (ref "C17") (pin "1") (pinfunction "1_1") (pintype "passive"))
      (node (ref "R9") (pin "2") (pinfunction "2_2") (pintype "passive"))
    )
    (net (code "20") (name "Net-(C16-Pad+)") (class "Default")
      (node (ref "C16") (pin "+") (pinfunction "+_+") (pintype "passive"))
      (node (ref "R31") (pin "2") (pinfunction "2_2") (pintype "passive"))
      (node (ref "R5") (pin "2") (pinfunction "2_2") (pintype "passive"))
    )
    (net (code "21") (name "Net-(C16-Pad-)") (class "Default")
      (node (ref "C16") (pin "-") (pinfunction "-_-") (pintype "passive"))
      (node (ref "C18") (pin "1") (pinfunction "1_1") (pintype "passive"))
      (node (ref "R10") (pin "2") (pinfunction "2_2") (pintype "passive"))
    )
    (net (code "22") (name "Net-(C19-Pad1)") (class "Default")
      (node (ref "C19") (pin "1") (pinfunction "1_1") (pintype "passive"))
      (node (ref "C20") (pin "1") (pinfunction "1_1") (pintype "passive"))
      (node (ref "C37") (pin "1") (pinfunction "1_1") (pintype "passive"))
      (node (ref "L1") (pin "1") (pinfunction "1_1") (pintype "passive"))
    )
    (net (code "23") (name "Net-(C19-Pad2)") (class "Default")
      (node (ref "C19") (pin "2") (pinfunction "2_2") (pintype "passive"))
      (node (ref "C21") (pin "1") (pinfunction "1_1") (pintype "passive"))
      (node (ref "C36") (pin "1") (pinfunction "1_1") (pintype "passive"))
      (node (ref "L3") (pin "1") (pinfunction "1_1") (pintype "passive"))
    )
    (net (code "24") (name "Net-(C22-Pad1)") (class "Default")
      (node (ref "C22") (pin "1") (pinfunction "1_1") (pintype "passive"))
      (node (ref "F1") (pin "A2") (pinfunction "A2_A2") (pintype "passive"))
    )
    (net (code "25") (name "Net-(C23-Pad2)") (class "Default")
      (node (ref "C23") (pin "2") (pinfunction "2_2") (pintype "passive"))
      (node (ref "U6") (pin "IN") (pinfunction "IN_IN") (pintype "input"))
    )
    (net (code "26") (name "Net-(C24-Pad1)") (class "Default")
      (node (ref "C24") (pin "1") (pinfunction "1_1") (pintype "passive"))
      (node (ref "C25") (pin "1") (pinfunction "1_1") (pintype "passive"))
      (node (ref "FB5") (pin "2") (pinfunction "2_2") (pintype "passive"))
      (node (ref "U6") (pin "VDD") (pinfunction "VDD_VDD") (pintype "power_in"))
    )
    (net (code "27") (name "Net-(C26-Pad1)") (class "Default")
      (node (ref "C26") (pin "1") (pinfunction "1_1") (pintype "passive"))
      (node (ref "C27") (pin "1") (pinfunction "1_1") (pintype "passive"))
      (node (ref "FB4") (pin "2") (pinfunction "2_2") (pintype "passive"))
      (node (ref "U6") (pin "VGG") (pinfunction "VGG_VGG") (pintype "power_in"))
    )
    (net (code "28") (name "Net-(C39-Pad2)") (class "Default")
      (node (ref "C39") (pin "2") (pinfunction "2_2") (pintype "passive"))
      (node (ref "F1") (pin "A1") (pinfunction "A1_A1") (pintype "passive"))
    )
    (net (code "29") (name "Net-(C43-Pad1)") (class "Default")
      (node (ref "C43") (pin "1") (pinfunction "1_1") (pintype "passive"))
      (node (ref "R24") (pin "1") (pinfunction "1_1") (pintype "passive"))
      (node (ref "R25") (pin "2") (pinfunction "2_2") (pintype "passive"))
    )
    (net (code "30") (name "Net-(C47-Pad1)") (class "Default")
      (node (ref "C47") (pin "1") (pinfunction "1_1") (pintype "passive"))
      (node (ref "R26") (pin "1") (pinfunction "1_1") (pintype "passive"))
      (node (ref "R27") (pin "2") (pinfunction "2_2") (pintype "passive"))
    )
    (net (code "31") (name "Net-(C50-Pad1)") (class "Default")
      (node (ref "C50") (pin "1") (pinfunction "1_1") (pintype "passive"))
      (node (ref "R31") (pin "1") (pinfunction "1_1") (pintype "passive"))
      (node (ref "R32") (pin "2") (pinfunction "2_2") (pintype "passive"))
    )
    (net (code "32") (name "Net-(C52-Pad1)") (class "Default")
      (node (ref "C52") (pin "1") (pinfunction "1_1") (pintype "passive"))
      (node (ref "R33") (pin "1") (pinfunction "1_1") (pintype "passive"))
      (node (ref "R34") (pin "2") (pinfunction "2_2") (pintype "passive"))
    )
    (net (code "33") (name "Net-(H1-A)") (class "Default")
      (node (ref "H1") (pin "1") (pinfunction "A_1") (pintype "passive"))
      (node (ref "R16") (pin "1") (pinfunction "1_1") (pintype "passive"))
    )
    (net (code "34") (name "Net-(H2-C)") (class "Default")
      (node (ref "H2") (pin "3") (pinfunction "C_3") (pintype "passive"))
      (node (ref "R11") (pin "2") (pinfunction "2_2") (pintype "passive"))
    )
    (net (code "35") (name "Net-(Q1-G)") (class "Default")
      (node (ref "Q1") (pin "1") (pinfunction "G_1") (pintype "passive"))
      (node (ref "R36") (pin "2") (pinfunction "2_2") (pintype "passive"))
      (node (ref "T1") (pin "C") (pinfunction "C_C") (pintype "passive"))
    )
    (net (code "36") (name "Net-(R14-S)") (class "Default")
      (node (ref "C31") (pin "2") (pinfunction "2_2") (pintype "passive"))
      (node (ref "R14") (pin "2") (pinfunction "S_2") (pintype "passive"))
      (node (ref "U7") (pin "2") (pinfunction "FB_2") (pintype "passive"))
    )
    (net (code "37") (name "Net-(R15-Pad1)") (class "Default")
      (node (ref "R15") (pin "1") (pinfunction "1_1") (pintype "passive"))
      (node (ref "T1") (pin "B") (pinfunction "B_B") (pintype "passive"))
    )
    (net (code "38") (name "Net-(R22-Pad1)") (class "Default")
      (node (ref "R22") (pin "1") (pinfunction "1_1") (pintype "passive"))
      (node (ref "T2") (pin "B") (pinfunction "B_B") (pintype "passive"))
    )
    (net (code "39") (name "Net-(U1A-OUTL)") (class "Default")
      (node (ref "R9") (pin "1") (pinfunction "1_1") (pintype "passive"))
      (node (ref "U1") (pin "6") (pinfunction "OUTL_6") (pintype "output"))
    )
    (net (code "40") (name "Net-(U1A-OUTR)") (class "Default")
      (node (ref "R10") (pin "1") (pinfunction "1_1") (pintype "passive"))
      (node (ref "U1") (pin "7") (pinfunction "OUTR_7") (pintype "output"))
    )
    (net (code "41") (name "Net-(U1B-CAPM)") (class "Default")
      (node (ref "C40") (pin "1") (pinfunction "1_1") (pintype "passive"))
      (node (ref "U1") (pin "4") (pinfunction "CAPM_4") (pintype "output"))
    )
    (net (code "42") (name "Net-(U1B-CAPP)") (class "Default")
      (node (ref "C40") (pin "2") (pinfunction "2_2") (pintype "passive"))
      (node (ref "U1") (pin "2") (pinfunction "CAPP_2") (pintype "output"))
    )
    (net (code "43") (name "Net-(U1B-LDOO)") (class "Default")
      (node (ref "C41") (pin "1") (pinfunction "1_1") (pintype "passive"))
      (node (ref "U1") (pin "18") (pinfunction "LDOO_18") (pintype "output"))
    )
    (net (code "44") (name "Net-(U1B-VNEG)") (class "Default")
      (node (ref "C11") (pin "1") (pinfunction "1_1") (pintype "passive"))
      (node (ref "U1") (pin "5") (pinfunction "VNEG_5") (pintype "output"))
    )
    (net (code "45") (name "Net-(U2-OE)") (class "Default")
      (node (ref "C35") (pin "1") (pinfunction "1_1") (pintype "passive"))
      (node (ref "R8") (pin "2") (pinfunction "2_2") (pintype "passive"))
      (node (ref "U2") (pin "2") (pinfunction "OE_2") (pintype "input"))
      (node (ref "U2") (pin "6") (pinfunction "VDD_6") (pintype "power_in"))
    )
    (net (code "46") (name "Net-(U2-SDA)") (class "Default")
      (node (ref "R7") (pin "2") (pinfunction "2_2") (pintype "passive"))
      (node (ref "U2") (pin "7") (pinfunction "SDA_7") (pintype "input"))
    )
    (net (code "47") (name "Net-(U3-EN)") (class "Default")
      (node (ref "C8") (pin "1") (pinfunction "1_1") (pintype "passive"))
      (node (ref "R1") (pin "1") (pinfunction "1_1") (pintype "passive"))
      (node (ref "U3") (pin "8") (pinfunction "EN_8") (pintype "input"))
    )
    (net (code "48") (name "Net-(U3-LO)") (class "Default")
      (node (ref "C10") (pin "2") (pinfunction "2_2") (pintype "passive"))
      (node (ref "U3") (pin "6") (pinfunction "LO_6") (pintype "input"))
    )
    (net (code "49") (name "Net-(U3-RF)") (class "Default")
      (node (ref "C39") (pin "1") (pinfunction "1_1") (pintype "passive"))
      (node (ref "U3") (pin "11") (pinfunction "RF_11") (pintype "output"))
    )
    (net (code "50") (name "Net-(U3-VPS1)") (class "Default")
      (node (ref "C3") (pin "1") (pinfunction "1_1") (pintype "passive"))
      (node (ref "C4") (pin "1") (pinfunction "1_1") (pintype "passive"))
      (node (ref "FB3") (pin "1") (pinfunction "1_1") (pintype "passive"))
      (node (ref "U3") (pin "7") (pinfunction "VPS1_7") (pintype "power_in"))
    )
    (net (code "51") (name "Net-(U3-VPS2)") (class "Default")
      (node (ref "C5") (pin "1") (pinfunction "1_1") (pintype "passive"))
      (node (ref "C6") (pin "1") (pinfunction "1_1") (pintype "passive"))
      (node (ref "FB2") (pin "1") (pinfunction "1_1") (pintype "passive"))
      (node (ref "U3") (pin "12") (pinfunction "VPS2_12") (pintype "power_in"))
    )
    (net (code "52") (name "Net-(U3-~{LO})") (class "Default")
      (node (ref "C9") (pin "2") (pinfunction "2_2") (pintype "passive"))
      (node (ref "U3") (pin "5") (pinfunction "~{LO}_5") (pintype "input"))
    )
    (net (code "53") (name "Net-(U4-EN)") (class "Default")
      (node (ref "C12") (pin "1") (pinfunction "1_1") (pintype "passive"))
      (node (ref "C2") (pin "1") (pinfunction "1_1") (pintype "passive"))
      (node (ref "FB1") (pin "2") (pinfunction "2_2") (pintype "passive"))
      (node (ref "U4") (pin "1") (pinfunction "IN_1") (pintype "input"))
      (node (ref "U4") (pin "3") (pinfunction "EN_3") (pintype "input"))
    )
    (net (code "54") (name "Net-(U5B-EN)") (class "Default")
      (node (ref "T2") (pin "C") (pinfunction "C_C") (pintype "passive"))
      (node (ref "U5") (pin "4") (pinfunction "EN_4") (pintype "input"))
    )
    (net (code "55") (name "Net-(U5B-IN)") (class "Default")
      (node (ref "C22") (pin "2") (pinfunction "2_2") (pintype "passive"))
      (node (ref "U5") (pin "2") (pinfunction "IN_2") (pintype "input"))
    )
    (net (code "56") (name "Net-(U5B-OUT)") (class "Default")
      (node (ref "C23") (pin "1") (pinfunction "1_1") (pintype "passive"))
      (node (ref "L5") (pin "2") (pinfunction "2_2") (pintype "passive"))
      (node (ref "U5") (pin "7") (pinfunction "OUT_7") (pintype "output"))
    )
    (net (code "57") (name "Net-(U7-EN)") (class "Default")
      (node (ref "R12") (pin "1") (pinfunction "1_1") (pintype "passive"))
      (node (ref "R13") (pin "1") (pinfunction "1_1") (pintype "passive"))
      (node (ref "U7") (pin "5") (pinfunction "EN_5") (pintype "input"))
    )
    (net (code "58") (name "Net-(U7-NR{slash}SS)") (class "Default")
      (node (ref "C29") (pin "1") (pinfunction "1_1") (pintype "passive"))
      (node (ref "U7") (pin "6") (pinfunction "NR/SS_6") (pintype "passive"))
    )
    (net (code "59") (name "Net-(U8A-+IN)") (class "Default")
      (node (ref "C49") (pin "1") (pinfunction "1_1") (pintype "passive"))
      (node (ref "R32") (pin "1") (pinfunction "1_1") (pintype "passive"))
      (node (ref "U8") (pin "3") (pinfunction "+IN_3") (pintype "input"))
    )
    (net (code "60") (name "Net-(U8A--IN)") (class "Default")
      (node (ref "C50") (pin "2") (pinfunction "2_2") (pintype "passive"))
      (node (ref "R33") (pin "2") (pinfunction "2_2") (pintype "passive"))
      (node (ref "U8") (pin "1") (pinfunction "OUT_1") (pintype "output"))
      (node (ref "U8") (pin "2") (pinfunction "-IN_2") (pintype "input"))
    )
    (net (code "61") (name "Net-(U8B-+IN)") (class "Default")
      (node (ref "C13") (pin "1") (pinfunction "1_1") (pintype "passive"))
      (node (ref "C14") (pin "1") (pinfunction "1_1") (pintype "passive"))
      (node (ref "R3") (pin "1") (pinfunction "1_1") (pintype "passive"))
      (node (ref "R4") (pin "2") (pinfunction "2_2") (pintype "passive"))
      (node (ref "R5") (pin "1") (pinfunction "1_1") (pintype "passive"))
      (node (ref "R6") (pin "1") (pinfunction "1_1") (pintype "passive"))
      (node (ref "U8") (pin "5") (pinfunction "+IN_5") (pintype "input"))
      (node (ref "U9") (pin "5") (pinfunction "+IN_5") (pintype "input"))
    )
    (net (code "62") (name "Net-(U8B--IN)") (class "Default")
      (node (ref "R29") (pin "1") (pinfunction "1_1") (pintype "passive"))
      (node (ref "R30") (pin "1") (pinfunction "1_1") (pintype "passive"))
      (node (ref "U8") (pin "6") (pinfunction "-IN_6") (pintype "input"))
    )
    (net (code "63") (name "Net-(U8C-+IN)") (class "Default")
      (node (ref "C52") (pin "2") (pinfunction "2_2") (pintype "passive"))
      (node (ref "U8") (pin "10") (pinfunction "+IN_10") (pintype "input"))
      (node (ref "U8") (pin "13") (pinfunction "-IN_13") (pintype "input"))
      (node (ref "U8") (pin "14") (pinfunction "OUT_14") (pintype "output"))
    )
    (net (code "64") (name "Net-(U8D-+IN)") (class "Default")
      (node (ref "C51") (pin "1") (pinfunction "1_1") (pintype "passive"))
      (node (ref "R34") (pin "1") (pinfunction "1_1") (pintype "passive"))
      (node (ref "U8") (pin "12") (pinfunction "+IN_12") (pintype "input"))
    )
    (net (code "65") (name "Net-(U9A-+IN)") (class "Default")
      (node (ref "C44") (pin "1") (pinfunction "1_1") (pintype "passive"))
      (node (ref "R27") (pin "1") (pinfunction "1_1") (pintype "passive"))
      (node (ref "U9") (pin "3") (pinfunction "+IN_3") (pintype "input"))
    )
    (net (code "66") (name "Net-(U9A--IN)") (class "Default")
      (node (ref "C47") (pin "2") (pinfunction "2_2") (pintype "passive"))
      (node (ref "U9") (pin "1") (pinfunction "OUT_1") (pintype "output"))
      (node (ref "U9") (pin "10") (pinfunction "+IN_10") (pintype "input"))
      (node (ref "U9") (pin "2") (pinfunction "-IN_2") (pintype "input"))
    )
    (net (code "67") (name "Net-(U9B--IN)") (class "Default")
      (node (ref "R19") (pin "1") (pinfunction "1_1") (pintype "passive"))
      (node (ref "R23") (pin "1") (pinfunction "1_1") (pintype "passive"))
      (node (ref "U9") (pin "6") (pinfunction "-IN_6") (pintype "input"))
    )
    (net (code "68") (name "Net-(U9D-+IN)") (class "Default")
      (node (ref "C42") (pin "1") (pinfunction "1_1") (pintype "passive"))
      (node (ref "R25") (pin "1") (pinfunction "1_1") (pintype "passive"))
      (node (ref "U9") (pin "12") (pinfunction "+IN_12") (pintype "input"))
    )
    (net (code "69") (name "Net-(U9D--IN)") (class "Default")
      (node (ref "C43") (pin "2") (pinfunction "2_2") (pintype "passive"))
      (node (ref "R26") (pin "2") (pinfunction "2_2") (pintype "passive"))
      (node (ref "U9") (pin "13") (pinfunction "-IN_13") (pintype "input"))
      (node (ref "U9") (pin "14") (pinfunction "OUT_14") (pintype "output"))
    )
    (net (code "70") (name "Net-(X1-GPIO4,GPCLK0)") (class "Default")
      (node (ref "R17") (pin "2") (pinfunction "2_2") (pintype "passive"))
      (node (ref "R18") (pin "2") (pinfunction "2_2") (pintype "passive"))
      (node (ref "X1") (pin "P1_7") (pinfunction "GPIO4,GPCLK0_P1_7") (pintype "bidirectional"))
    )
    (net (code "71") (name "Net-(X1-GPIO11_SCLK)") (class "Default")
      (node (ref "R15") (pin "2") (pinfunction "2_2") (pintype "passive"))
      (node (ref "X1") (pin "P1_23") (pinfunction "GPIO11_SCLK_P1_23") (pintype "bidirectional"))
    )
    (net (code "72") (name "Net-(X1-GPIO14,UART0_TXD)") (class "Default")
      (node (ref "X1") (pin "P1_8") (pinfunction "GPIO14,UART0_TXD_P1_8") (pintype "bidirectional"))
      (node (ref "X11") (pin "1") (pinfunction "P_1") (pintype "passive"))
    )
    (net (code "73") (name "Net-(X1-GPIO15,UART0_RXD)") (class "Default")
      (node (ref "X1") (pin "P1_10") (pinfunction "GPIO15,UART0_RXD_P1_10") (pintype "bidirectional"))
      (node (ref "X10") (pin "1") (pinfunction "P_1") (pintype "passive"))
    )
    (net (code "74") (name "Net-(X9-P)") (class "Default")
      (node (ref "U6") (pin "OUT") (pinfunction "OUT_OUT") (pintype "output"))
      (node (ref "X9") (pin "1") (pinfunction "P_1") (pintype "passive"))
    )
    (net (code "75") (name "PA_EN") (class "Default")
      (node (ref "R12") (pin "2") (pinfunction "2_2") (pintype "passive"))
      (node (ref "X1") (pin "P1_26") (pinfunction "GPIO7,SPI0_CE1_P1_26") (pintype "bidirectional"))
    )
    (net (code "76") (name "PCM_CLK") (class "Default")
      (node (ref "U1") (pin "13") (pinfunction "BCK_13") (pintype "input"))
      (node (ref "X1") (pin "P5_3") (pinfunction "GPIO28_P5_3") (pintype "bidirectional"))
    )
    (net (code "77") (name "PCM_DOUT") (class "Default")
      (node (ref "U1") (pin "14") (pinfunction "DIN_14") (pintype "input"))
      (node (ref "X1") (pin "P5_6") (pinfunction "GPIO31_P5_6") (pintype "bidirectional"))
    )
    (net (code "78") (name "PCM_FS") (class "Default")
      (node (ref "U1") (pin "15") (pinfunction "LRCLK_15") (pintype "input"))
      (node (ref "X1") (pin "P5_4") (pinfunction "GPIO29_P5_4") (pintype "bidirectional"))
    )
    (net (code "79") (name "PRE_EN") (class "Default")
      (node (ref "R21") (pin "1") (pinfunction "1_1") (pintype "passive"))
      (node (ref "R22") (pin "2") (pinfunction "2_2") (pintype "passive"))
      (node (ref "X1") (pin "P1_24") (pinfunction "GPIO8,SPI0_CE0_P1_24") (pintype "bidirectional"))
    )
    (net (code "80") (name "REL") (class "Default")
      (node (ref "Q1") (pin "3") (pinfunction "D_3") (pintype "passive"))
      (node (ref "X25") (pin "3") (pinfunction "3_3") (pintype "passive"))
    )
    (net (code "81") (name "REL_FB") (class "Default")
      (node (ref "X1") (pin "P1_11") (pinfunction "GPIO17_P1_11") (pintype "bidirectional"))
      (node (ref "X25") (pin "9") (pinfunction "9_9") (pintype "passive"))
    )
    (net (code "82") (name "SCL") (class "Default")
      (node (ref "U2") (pin "8") (pinfunction "SCL_8") (pintype "input"))
      (node (ref "X1") (pin "P1_5") (pinfunction "GPIO3,I2C0_SCL_P1_5") (pintype "bidirectional"))
      (node (ref "X5") (pin "1") (pinfunction "P_1") (pintype "passive"))
    )
    (net (code "83") (name "SDA") (class "Default")
      (node (ref "R7") (pin "1") (pinfunction "1_1") (pintype "passive"))
      (node (ref "X1") (pin "P1_3") (pinfunction "GPIO2,I2C0_SDA_P1_3") (pintype "bidirectional"))
      (node (ref "X4") (pin "1") (pinfunction "P_1") (pintype "passive"))
    )
    (net (code "84") (name "STAT") (class "Default")
      (node (ref "H2") (pin "1") (pinfunction "A_1") (pintype "passive"))
      (node (ref "X1") (pin "P1_19") (pinfunction "GPIO10_MOSI_P1_19") (pintype "bidirectional"))
    )
    (net (code "85") (name "VGG") (class "Default")
      (node (ref "C28") (pin "1") (pinfunction "1_1") (pintype "passive"))
      (node (ref "C31") (pin "1") (pinfunction "1_1") (pintype "passive"))
      (node (ref "C34") (pin "1") (pinfunction "1_1") (pintype "passive"))
      (node (ref "FB4") (pin "1") (pinfunction "1_1") (pintype "passive"))
      (node (ref "R14") (pin "1") (pinfunction "A_1") (pintype "passive"))
      (node (ref "U7") (pin "1") (pinfunction "OUT_1") (pintype "power_in"))
    )
    (net (code "86") (name "unconnected-(U2-CLK--Pad5)") (class "Default")
      (node (ref "U2") (pin "5") (pinfunction "CLK-_5") (pintype "output"))
    )
    (net (code "87") (name "unconnected-(U4-BYP-Pad4)") (class "Default")
      (node (ref "U4") (pin "4") (pinfunction "BYP_4") (pintype "passive"))
    )
    (net (code "88") (name "unconnected-(U7-DNC-Pad7)") (class "Default")
      (node (ref "U7") (pin "7") (pinfunction "DNC_7") (pintype "no_connect"))
    )
    (net (code "89") (name "unconnected-(U7-NC-Pad3)") (class "Default")
      (node (ref "U7") (pin "3") (pinfunction "NC_3") (pintype "no_connect"))
    )
    (net (code "90") (name "unconnected-(X1-GPIO18-PadP1_12)") (class "Default")
      (node (ref "X1") (pin "P1_12") (pinfunction "GPIO18_P1_12") (pintype "bidirectional"))
    )
    (net (code "91") (name "unconnected-(X1-GPIO22-PadP1_15)") (class "Default")
      (node (ref "X1") (pin "P1_15") (pinfunction "GPIO22_P1_15") (pintype "bidirectional"))
    )
    (net (code "92") (name "unconnected-(X1-GPIO23-PadP1_16)") (class "Default")
      (node (ref "X1") (pin "P1_16") (pinfunction "GPIO23_P1_16") (pintype "bidirectional"))
    )
    (net (code "93") (name "unconnected-(X1-GPIO24-PadP1_18)") (class "Default")
      (node (ref "X1") (pin "P1_18") (pinfunction "GPIO24_P1_18") (pintype "bidirectional"))
    )
    (net (code "94") (name "unconnected-(X1-GPIO25-PadP1_22)") (class "Default")
      (node (ref "X1") (pin "P1_22") (pinfunction "GPIO25_P1_22") (pintype "bidirectional"))
    )
    (net (code "95") (name "unconnected-(X1-GPIO27-PadP1_13)") (class "Default")
      (node (ref "X1") (pin "P1_13") (pinfunction "GPIO27_P1_13") (pintype "bidirectional"))
    )
    (net (code "96") (name "unconnected-(X1-GPIO30-PadP5_5)") (class "Default")
      (node (ref "X1") (pin "P5_5") (pinfunction "GPIO30_P5_5") (pintype "bidirectional"))
    )
    (net (code "97") (name "unconnected-(X25-Pad10)") (class "Default")
      (node (ref "X25") (pin "10") (pinfunction "10_10") (pintype "passive"))
    )
  )
)
